# untitled.net
KiCad netlist of a schematic drawn in EAGLE
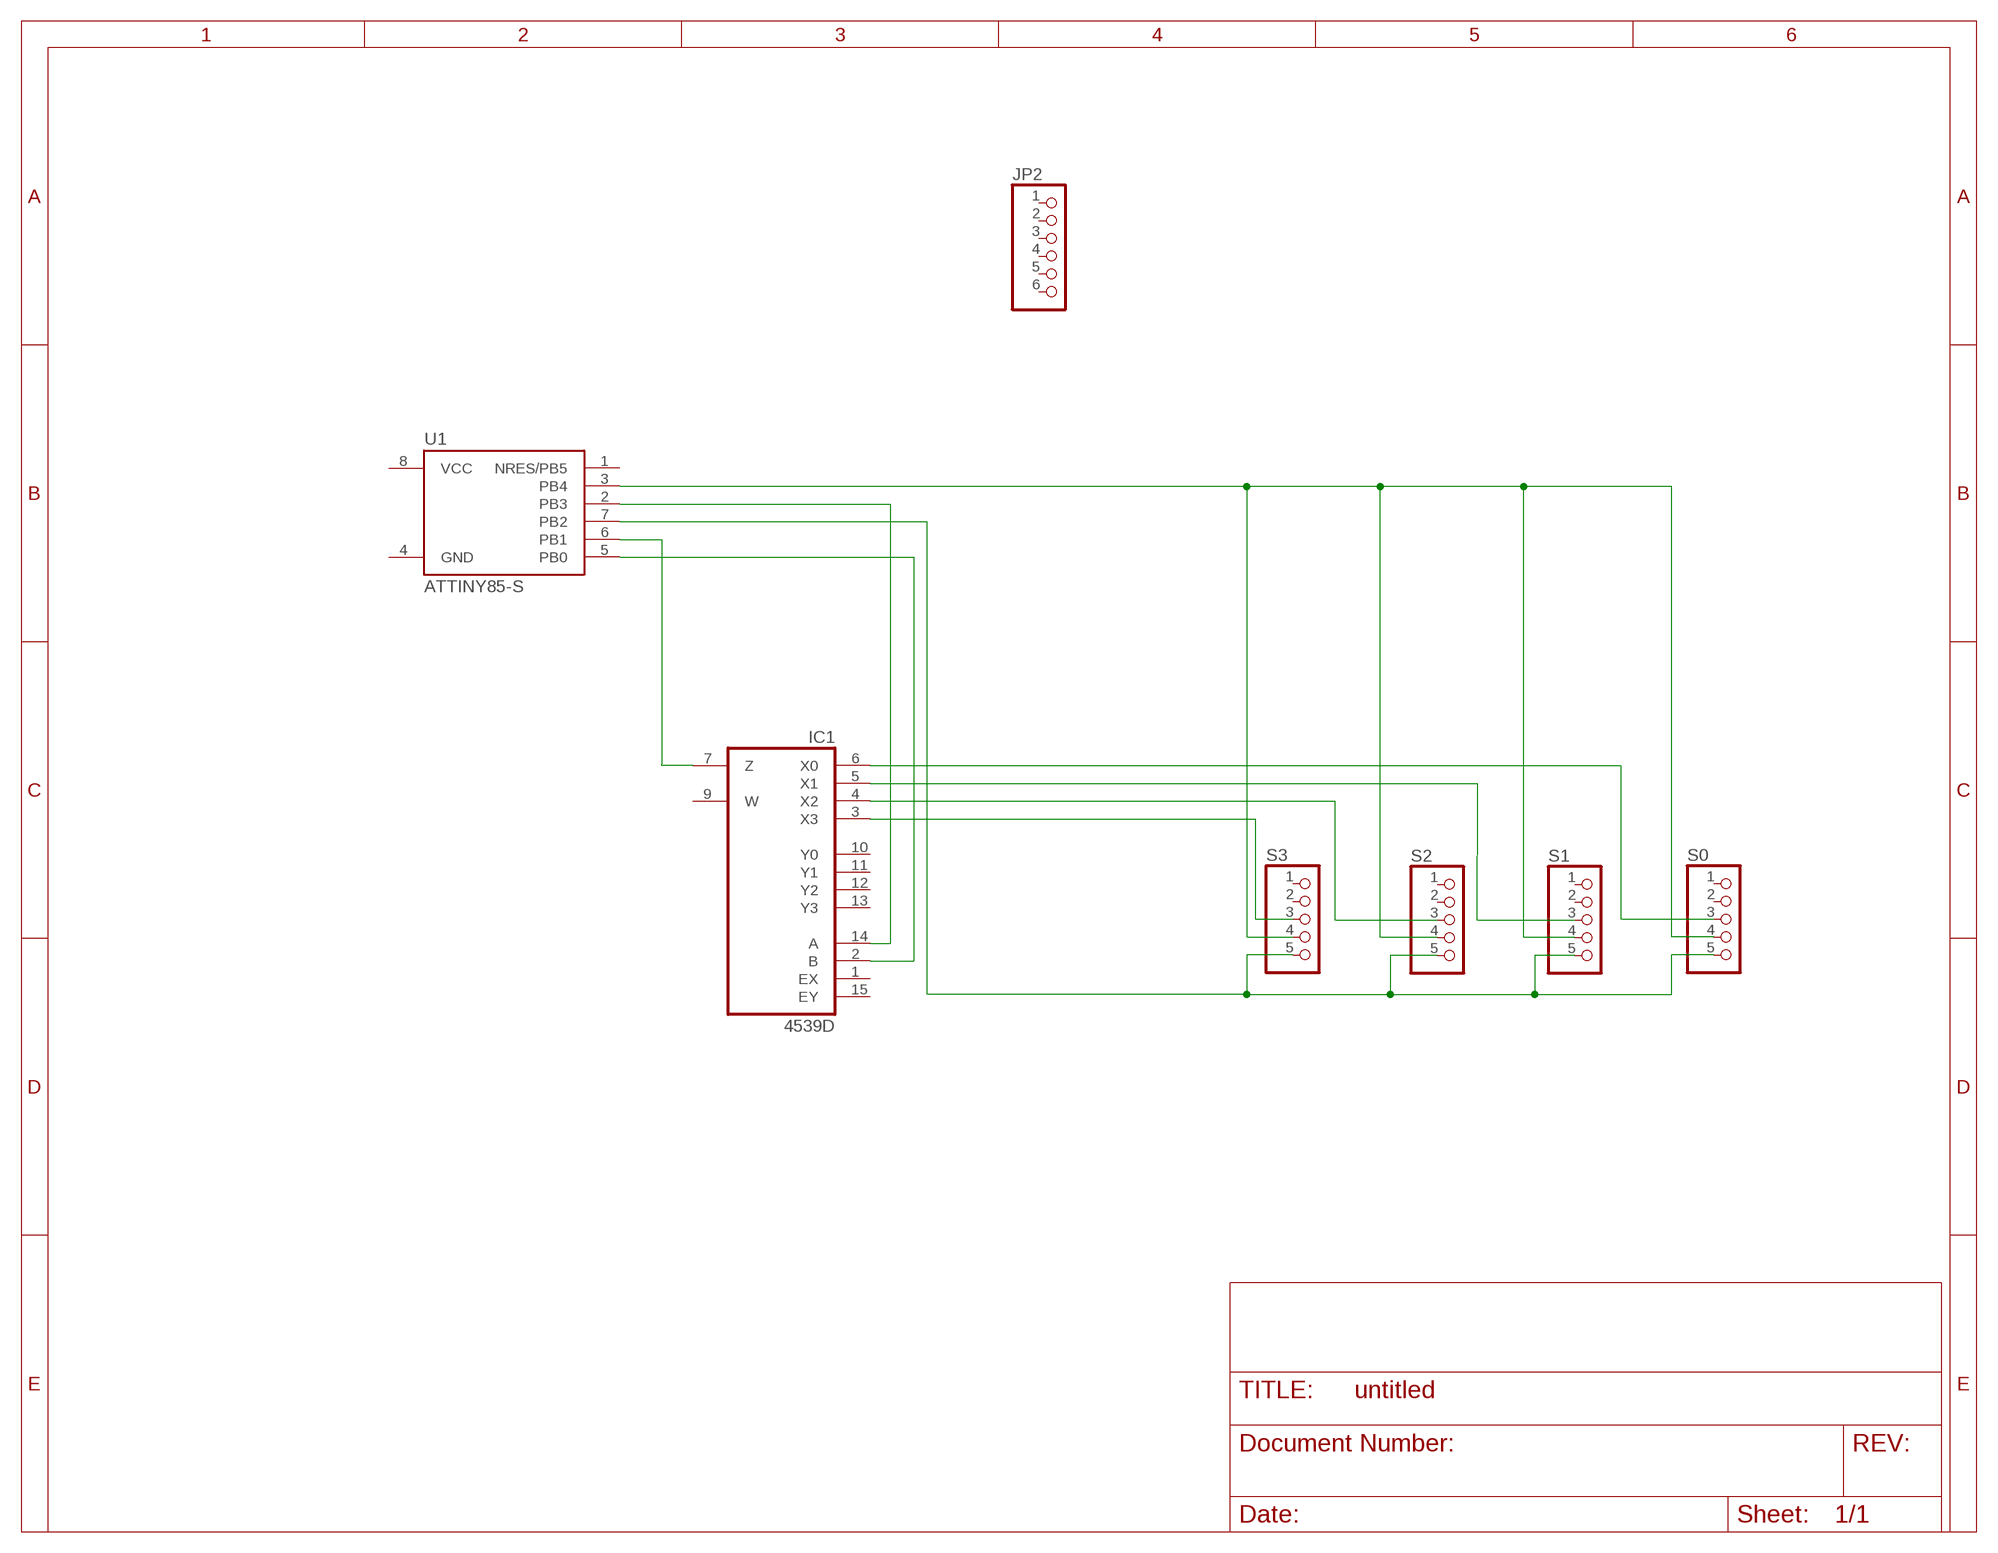
[diagram p0: schematic, sheet 1]

(export (version "E")
  (design (tool "Eeschema 10.0.6"))
  (components
    (comp (ref "IC1")
      (value "4539D")
      (footprint "eagle-import:SO16")
      (libsource (lib "eagle-import") (part "4539D"))
    )
    (comp (ref "JP2")
      (value "PINHD-1X6")
      (footprint "eagle-import:1X06")
      (libsource (lib "eagle-import") (part "PINHD-1X6"))
    )
    (comp (ref "S0")
      (value "PINHD-1X5")
      (footprint "eagle-import:1X05")
      (libsource (lib "eagle-import") (part "PINHD-1X5"))
    )
    (comp (ref "S1")
      (value "PINHD-1X5")
      (footprint "eagle-import:1X05")
      (libsource (lib "eagle-import") (part "PINHD-1X5"))
    )
    (comp (ref "S2")
      (value "PINHD-1X5")
      (footprint "eagle-import:1X05")
      (libsource (lib "eagle-import") (part "PINHD-1X5"))
    )
    (comp (ref "S3")
      (value "PINHD-1X5")
      (footprint "eagle-import:1X05")
      (libsource (lib "eagle-import") (part "PINHD-1X5"))
    )
    (comp (ref "U1")
      (value "ATTINY85-S")
      (footprint "eagle-import:SOIC8_EIAJ_208MIL")
      (libsource (lib "eagle-import") (part "ATTINY85S-"))
    )
  )
  (nets
    (net (code "1") (name "/GND") (class "Default")
      (node (ref "U1") (pin "4") (pinfunction "GND_4") (pintype "power_in"))
    )
    (net (code "2") (name "/VCC") (class "Default")
      (node (ref "U1") (pin "8") (pinfunction "VCC_8") (pintype "power_in"))
    )
    (net (code "3") (name "Net-(IC1A-A)") (class "Default")
      (node (ref "IC1") (pin "14") (pinfunction "A_14") (pintype "input"))
      (node (ref "U1") (pin "2") (pinfunction "PB3_2") (pintype "bidirectional"))
    )
    (net (code "4") (name "Net-(IC1A-B)") (class "Default")
      (node (ref "IC1") (pin "2") (pinfunction "B_2") (pintype "input"))
      (node (ref "U1") (pin "5") (pinfunction "PB0_5") (pintype "bidirectional"))
    )
    (net (code "5") (name "Net-(IC1A-X1)") (class "Default")
      (node (ref "IC1") (pin "5") (pinfunction "X1_5") (pintype "input"))
      (node (ref "S1") (pin "3") (pinfunction "3_3") (pintype "passive"))
    )
    (net (code "6") (name "Net-(IC1A-X2)") (class "Default")
      (node (ref "IC1") (pin "4") (pinfunction "X2_4") (pintype "input"))
      (node (ref "S2") (pin "3") (pinfunction "3_3") (pintype "passive"))
    )
    (net (code "7") (name "Net-(IC1A-X3)") (class "Default")
      (node (ref "IC1") (pin "3") (pinfunction "X3_3") (pintype "input"))
      (node (ref "S3") (pin "3") (pinfunction "3_3") (pintype "passive"))
    )
    (net (code "8") (name "Net-(IC1A-Z)") (class "Default")
      (node (ref "IC1") (pin "7") (pinfunction "Z_7") (pintype "tri_state"))
      (node (ref "U1") (pin "6") (pinfunction "PB1_6") (pintype "bidirectional"))
    )
    (net (code "9") (name "Net-(U1-PB2)") (class "Default")
      (node (ref "S0") (pin "5") (pinfunction "5_5") (pintype "passive"))
      (node (ref "S1") (pin "5") (pinfunction "5_5") (pintype "passive"))
      (node (ref "S2") (pin "5") (pinfunction "5_5") (pintype "passive"))
      (node (ref "U1") (pin "7") (pinfunction "PB2_7") (pintype "bidirectional"))
    )
    (net (code "10") (name "Net-(U1-PB4)") (class "Default")
      (node (ref "S0") (pin "4") (pinfunction "4_4") (pintype "passive"))
      (node (ref "S1") (pin "4") (pinfunction "4_4") (pintype "passive"))
      (node (ref "S2") (pin "4") (pinfunction "4_4") (pintype "passive"))
      (node (ref "S3") (pin "4") (pinfunction "4_4") (pintype "passive"))
      (node (ref "U1") (pin "3") (pinfunction "PB4_3") (pintype "bidirectional"))
    )
    (net (code "11") (name "unconnected-(IC1A-EX-Pad1)") (class "Default")
      (node (ref "IC1") (pin "1") (pinfunction "EX_1") (pintype "input"))
    )
    (net (code "12") (name "unconnected-(IC1A-EY-Pad15)") (class "Default")
      (node (ref "IC1") (pin "15") (pinfunction "EY_15") (pintype "input"))
    )
    (net (code "13") (name "unconnected-(IC1A-W-Pad9)") (class "Default")
      (node (ref "IC1") (pin "9") (pinfunction "W_9") (pintype "tri_state"))
    )
    (net (code "14") (name "unconnected-(IC1A-X0-Pad6)") (class "Default")
      (node (ref "IC1") (pin "6") (pinfunction "X0_6") (pintype "input"))
    )
    (net (code "15") (name "unconnected-(IC1A-Y0-Pad10)") (class "Default")
      (node (ref "IC1") (pin "10") (pinfunction "Y0_10") (pintype "input"))
    )
    (net (code "16") (name "unconnected-(IC1A-Y1-Pad11)") (class "Default")
      (node (ref "IC1") (pin "11") (pinfunction "Y1_11") (pintype "input"))
    )
    (net (code "17") (name "unconnected-(IC1A-Y2-Pad12)") (class "Default")
      (node (ref "IC1") (pin "12") (pinfunction "Y2_12") (pintype "input"))
    )
    (net (code "18") (name "unconnected-(IC1A-Y3-Pad13)") (class "Default")
      (node (ref "IC1") (pin "13") (pinfunction "Y3_13") (pintype "input"))
    )
    (net (code "19") (name "unconnected-(JP2-Pad1)") (class "Default")
      (node (ref "JP2") (pin "1") (pinfunction "1_1") (pintype "passive"))
    )
    (net (code "20") (name "unconnected-(JP2-Pad2)") (class "Default")
      (node (ref "JP2") (pin "2") (pinfunction "2_2") (pintype "passive"))
    )
    (net (code "21") (name "unconnected-(JP2-Pad3)") (class "Default")
      (node (ref "JP2") (pin "3") (pinfunction "3_3") (pintype "passive"))
    )
    (net (code "22") (name "unconnected-(JP2-Pad4)") (class "Default")
      (node (ref "JP2") (pin "4") (pinfunction "4_4") (pintype "passive"))
    )
    (net (code "23") (name "unconnected-(JP2-Pad5)") (class "Default")
      (node (ref "JP2") (pin "5") (pinfunction "5_5") (pintype "passive"))
    )
    (net (code "24") (name "unconnected-(JP2-Pad6)") (class "Default")
      (node (ref "JP2") (pin "6") (pinfunction "6_6") (pintype "passive"))
    )
    (net (code "25") (name "unconnected-(S0-Pad1)") (class "Default")
      (node (ref "S0") (pin "1") (pinfunction "1_1") (pintype "passive"))
    )
    (net (code "26") (name "unconnected-(S0-Pad2)") (class "Default")
      (node (ref "S0") (pin "2") (pinfunction "2_2") (pintype "passive"))
    )
    (net (code "27") (name "unconnected-(S0-Pad3)") (class "Default")
      (node (ref "S0") (pin "3") (pinfunction "3_3") (pintype "passive"))
    )
    (net (code "28") (name "unconnected-(S1-Pad1)") (class "Default")
      (node (ref "S1") (pin "1") (pinfunction "1_1") (pintype "passive"))
    )
    (net (code "29") (name "unconnected-(S1-Pad2)") (class "Default")
      (node (ref "S1") (pin "2") (pinfunction "2_2") (pintype "passive"))
    )
    (net (code "30") (name "unconnected-(S2-Pad1)") (class "Default")
      (node (ref "S2") (pin "1") (pinfunction "1_1") (pintype "passive"))
    )
    (net (code "31") (name "unconnected-(S2-Pad2)") (class "Default")
      (node (ref "S2") (pin "2") (pinfunction "2_2") (pintype "passive"))
    )
    (net (code "32") (name "unconnected-(S3-Pad1)") (class "Default")
      (node (ref "S3") (pin "1") (pinfunction "1_1") (pintype "passive"))
    )
    (net (code "33") (name "unconnected-(S3-Pad2)") (class "Default")
      (node (ref "S3") (pin "2") (pinfunction "2_2") (pintype "passive"))
    )
    (net (code "34") (name "unconnected-(S3-Pad5)") (class "Default")
      (node (ref "S3") (pin "5") (pinfunction "5_5") (pintype "passive"))
    )
    (net (code "35") (name "unconnected-(U1-NRES{slash}PB5-Pad1)") (class "Default")
      (node (ref "U1") (pin "1") (pinfunction "NRES/PB5_1") (pintype "bidirectional"))
    )
  )
)
